# Rocket-Switch-Interface_1_0.net
KiCad netlist of a schematic drawn in EAGLE
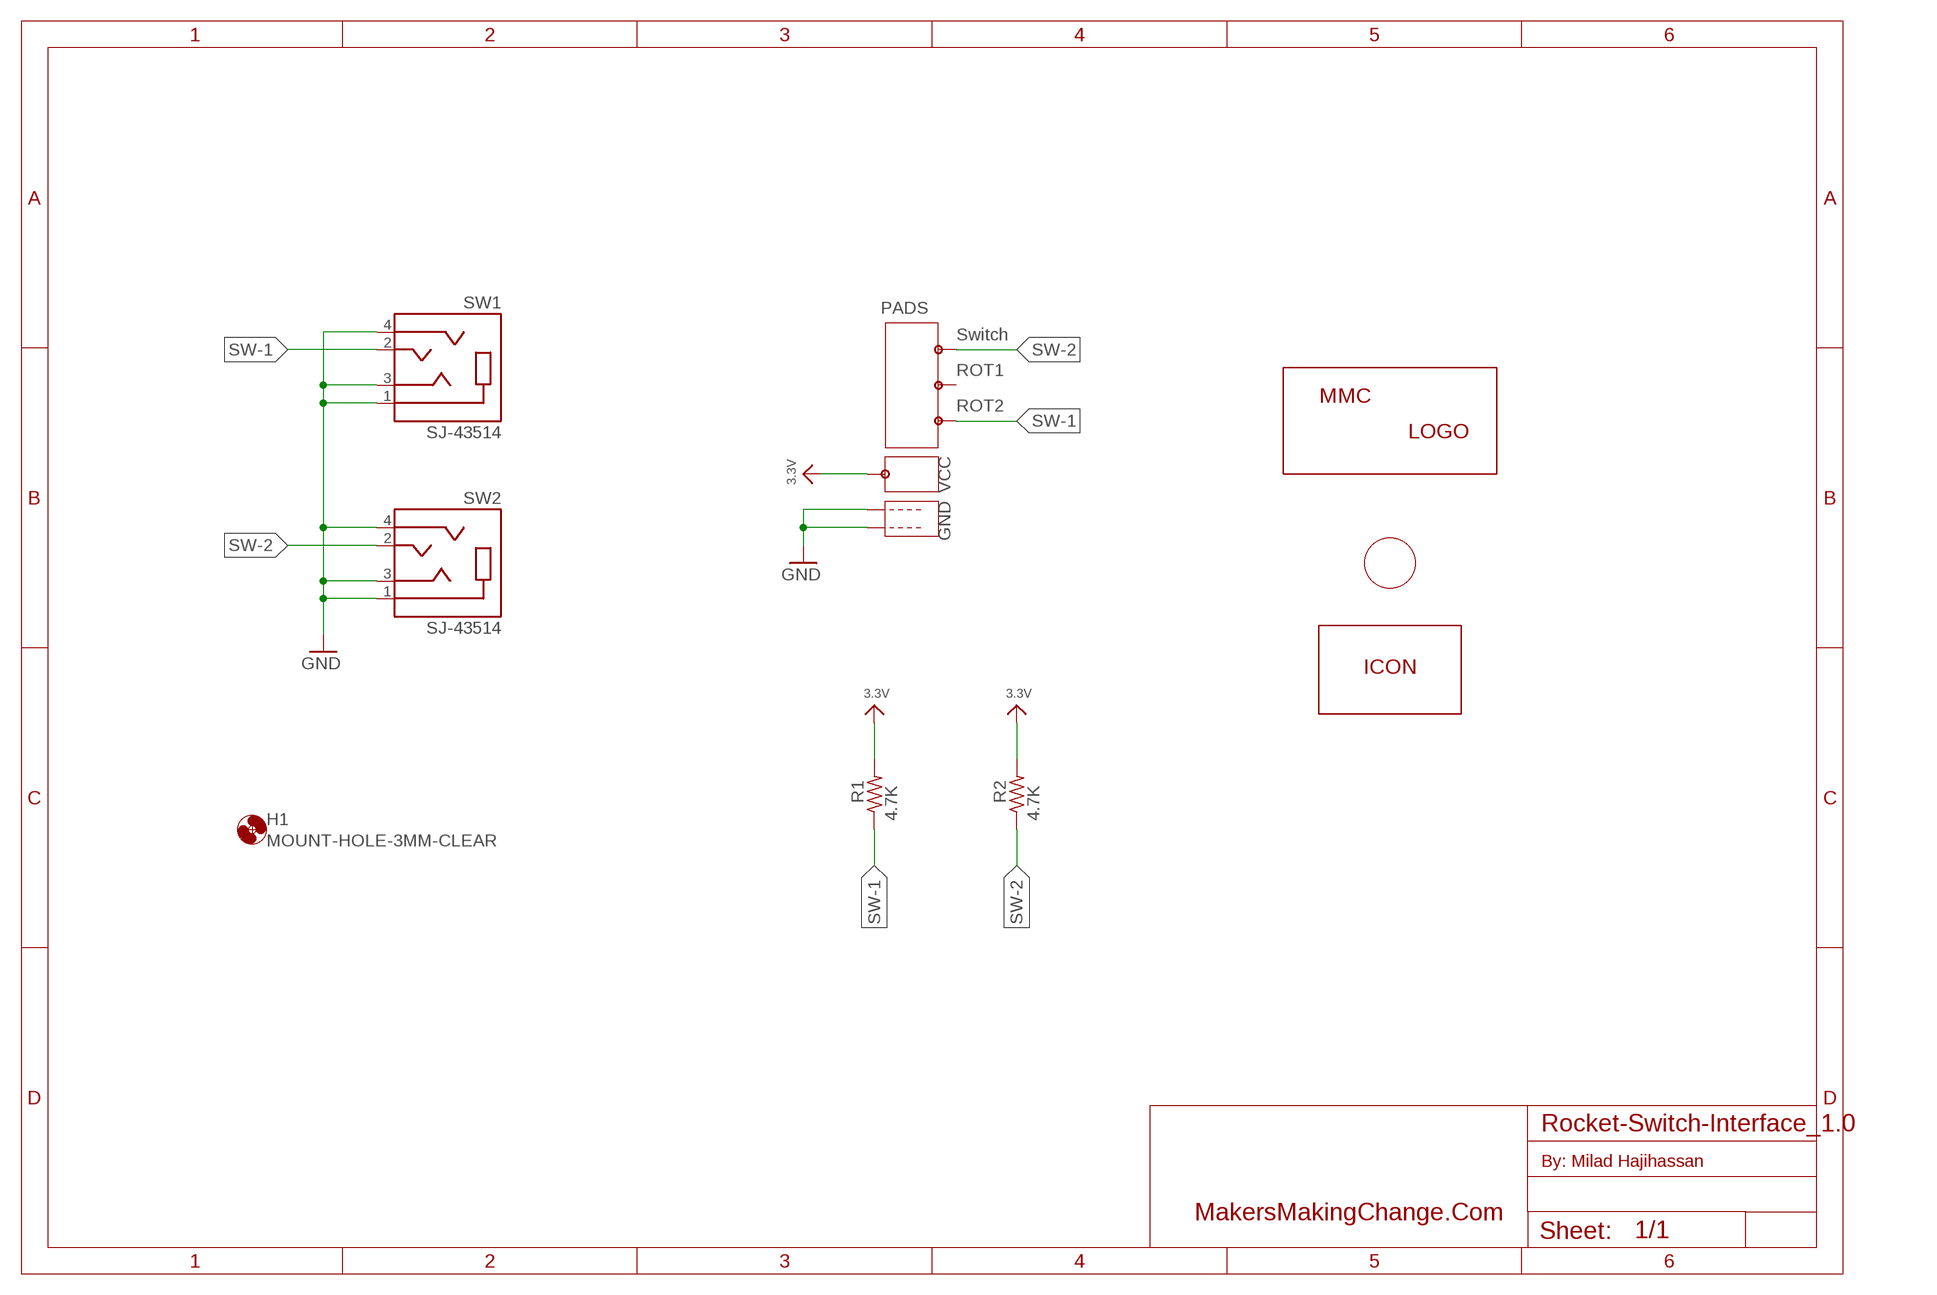
[diagram p0: schematic, sheet 1]

(export (version "E")
  (design (tool "Eeschema 10.0.6"))
  (components
    (comp (ref "H1")
      (value "MOUNT-HOLE-3MM-CLEAR")
      (footprint "eagle-import:HOLE-3MM-CLEAR")
      (libsource (lib "eagle-import") (part "MOUNT-HOLE-3MM-CLEAR"))
    )
    (comp (ref "LABEL_BACKGROUND")
      (value "MMC_ICON-ROCKET-SW")
      (footprint "eagle-import:ICON_ROCKET-SWITCH")
      (libsource (lib "eagle-import") (part "MMC_ICON-ROCKET-SW"))
    )
    (comp (ref "LABEL_DEVICE")
      (value "MMC_LABEL-ROCKET-SW")
      (footprint "eagle-import:LABEL-ROCKET-SWITCH")
      (libsource (lib "eagle-import") (part "MMC_LABEL-ROCKET-SW"))
    )
    (comp (ref "LABEL_LOGO")
      (value "MMC_LOGO-XSM")
      (footprint "eagle-import:MMC_X-SMALL_LOGO")
      (libsource (lib "eagle-import") (part "MMC_LOGO-XSM"))
    )
    (comp (ref "PADS")
      (value "PADS-ROTARY-TRINKEY")
      (footprint "eagle-import:PADS-ROTARY-TRINKEY")
      (libsource (lib "eagle-import") (part "PADS-ROTARY-TRINKEY"))
    )
    (comp (ref "R1")
      (value "4.7K")
      (footprint "eagle-import:RESISTOR_0204_5")
      (libsource (lib "eagle-import") (part "RESISTOR-US-0204/5"))
    )
    (comp (ref "R2")
      (value "4.7K")
      (footprint "eagle-import:RESISTOR_0204_5")
      (libsource (lib "eagle-import") (part "RESISTOR-US-0204/5"))
    )
    (comp (ref "SW1")
      (value "SJ-43514")
      (footprint "eagle-import:CUI_SJ-43514")
      (libsource (lib "eagle-import") (part "SJ-43514"))
    )
    (comp (ref "SW2")
      (value "SJ-43514")
      (footprint "eagle-import:CUI_SJ-43514")
      (libsource (lib "eagle-import") (part "SJ-43514"))
    )
  )
  (nets
    (net (code "1") (name "3.3V") (class "Default")
      (node (ref "PADS") (pin "P$VCC") (pinfunction "P$VCC_P$VCC") (pintype "passive"))
      (node (ref "R1") (pin "2") (pinfunction "2_2") (pintype "passive"))
      (node (ref "R2") (pin "2") (pinfunction "2_2") (pintype "passive"))
    )
    (net (code "2") (name "GND") (class "Default")
      (node (ref "PADS") (pin "P$GND1") (pinfunction "P$GND1_P$GND1") (pintype "passive"))
      (node (ref "PADS") (pin "P$GND2") (pinfunction "P$GND2_P$GND2") (pintype "passive"))
      (node (ref "SW1") (pin "1") (pinfunction "SLEEVE_1") (pintype "passive"))
      (node (ref "SW1") (pin "3") (pinfunction "RING1_3") (pintype "passive"))
      (node (ref "SW1") (pin "4") (pinfunction "RING2_4") (pintype "passive"))
      (node (ref "SW2") (pin "1") (pinfunction "SLEEVE_1") (pintype "passive"))
      (node (ref "SW2") (pin "3") (pinfunction "RING1_3") (pintype "passive"))
      (node (ref "SW2") (pin "4") (pinfunction "RING2_4") (pintype "passive"))
    )
    (net (code "3") (name "SW-1") (class "Default")
      (node (ref "PADS") (pin "P$ROT2") (pinfunction "P$ROT2_P$ROT2") (pintype "passive"))
      (node (ref "R1") (pin "1") (pinfunction "1_1") (pintype "passive"))
      (node (ref "SW1") (pin "2") (pinfunction "TIP_2") (pintype "passive"))
    )
    (net (code "4") (name "SW-2") (class "Default")
      (node (ref "PADS") (pin "P$SW") (pinfunction "P$SW_P$SW") (pintype "passive"))
      (node (ref "R2") (pin "1") (pinfunction "1_1") (pintype "passive"))
      (node (ref "SW2") (pin "2") (pinfunction "TIP_2") (pintype "passive"))
    )
    (net (code "5") (name "unconnected-(PADS-PadP$ROT1)") (class "Default")
      (node (ref "PADS") (pin "P$ROT1") (pinfunction "P$ROT1_P$ROT1") (pintype "passive"))
    )
  )
)
